# EIB_A79024-001.net
KiCad netlist of a schematic drawn in EAGLE
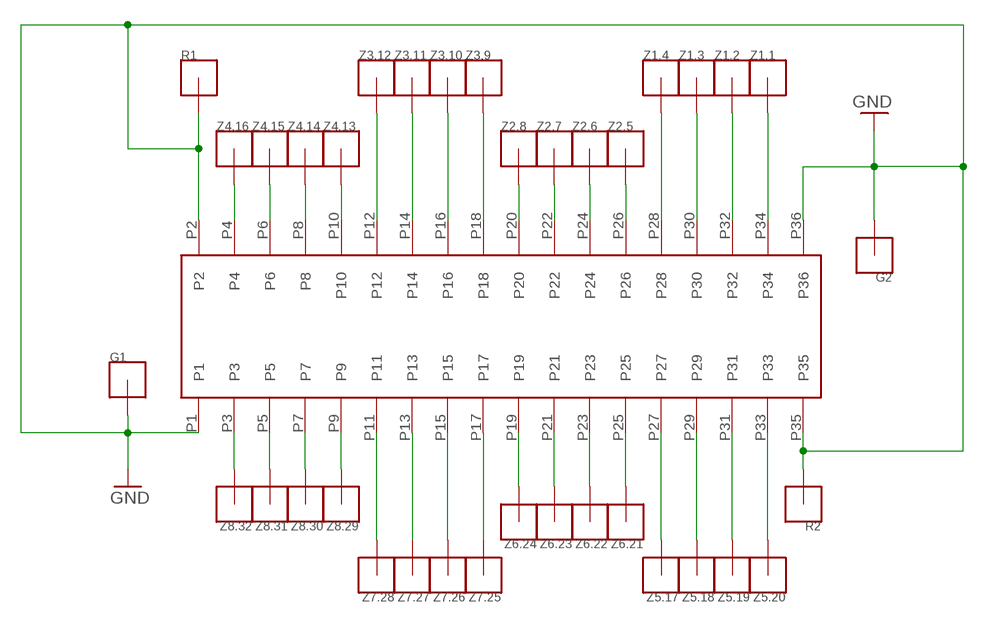
[diagram p0: schematic, sheet 1]

(export (version "E")
  (design (tool "Eeschema 10.0.6"))
  (components
    (comp (ref "A79024")
      (value "OMNETICS")
      (footprint "eagle-import:A79024")
      (libsource (lib "eagle-import") (part "OMNETICS"))
    )
    (comp (ref "G1")
      (value "S_P_HOLE")
      (footprint "eagle-import:S_P_HOLE")
      (libsource (lib "eagle-import") (part "S_P_HOLE"))
    )
    (comp (ref "G2")
      (value "S_P_HOLE")
      (footprint "eagle-import:S_P_HOLE")
      (libsource (lib "eagle-import") (part "S_P_HOLE"))
    )
    (comp (ref "R1")
      (value "S_P_HOLE")
      (footprint "eagle-import:S_P_HOLE")
      (libsource (lib "eagle-import") (part "S_P_HOLE"))
    )
    (comp (ref "R2")
      (value "S_P_HOLE")
      (footprint "eagle-import:S_P_HOLE")
      (libsource (lib "eagle-import") (part "S_P_HOLE"))
    )
    (comp (ref "Z1.1")
      (value "S_P_HOLE")
      (footprint "eagle-import:S_P_HOLE")
      (libsource (lib "eagle-import") (part "S_P_HOLE"))
    )
    (comp (ref "Z1.2")
      (value "S_P_HOLE")
      (footprint "eagle-import:S_P_HOLE")
      (libsource (lib "eagle-import") (part "S_P_HOLE"))
    )
    (comp (ref "Z1.3")
      (value "S_P_HOLE")
      (footprint "eagle-import:S_P_HOLE")
      (libsource (lib "eagle-import") (part "S_P_HOLE"))
    )
    (comp (ref "Z1.4")
      (value "S_P_HOLE")
      (footprint "eagle-import:S_P_HOLE")
      (libsource (lib "eagle-import") (part "S_P_HOLE"))
    )
    (comp (ref "Z2.5")
      (value "S_P_HOLE")
      (footprint "eagle-import:S_P_HOLE")
      (libsource (lib "eagle-import") (part "S_P_HOLE"))
    )
    (comp (ref "Z2.6")
      (value "S_P_HOLE")
      (footprint "eagle-import:S_P_HOLE")
      (libsource (lib "eagle-import") (part "S_P_HOLE"))
    )
    (comp (ref "Z2.7")
      (value "S_P_HOLE")
      (footprint "eagle-import:S_P_HOLE")
      (libsource (lib "eagle-import") (part "S_P_HOLE"))
    )
    (comp (ref "Z2.8")
      (value "S_P_HOLE")
      (footprint "eagle-import:S_P_HOLE")
      (libsource (lib "eagle-import") (part "S_P_HOLE"))
    )
    (comp (ref "Z3.9")
      (value "S_P_HOLE")
      (footprint "eagle-import:S_P_HOLE")
      (libsource (lib "eagle-import") (part "S_P_HOLE"))
    )
    (comp (ref "Z3.10")
      (value "S_P_HOLE")
      (footprint "eagle-import:S_P_HOLE")
      (libsource (lib "eagle-import") (part "S_P_HOLE"))
    )
    (comp (ref "Z3.11")
      (value "S_P_HOLE")
      (footprint "eagle-import:S_P_HOLE")
      (libsource (lib "eagle-import") (part "S_P_HOLE"))
    )
    (comp (ref "Z3.12")
      (value "S_P_HOLE")
      (footprint "eagle-import:S_P_HOLE")
      (libsource (lib "eagle-import") (part "S_P_HOLE"))
    )
    (comp (ref "Z4.13")
      (value "S_P_HOLE")
      (footprint "eagle-import:S_P_HOLE")
      (libsource (lib "eagle-import") (part "S_P_HOLE"))
    )
    (comp (ref "Z4.14")
      (value "S_P_HOLE")
      (footprint "eagle-import:S_P_HOLE")
      (libsource (lib "eagle-import") (part "S_P_HOLE"))
    )
    (comp (ref "Z4.15")
      (value "S_P_HOLE")
      (footprint "eagle-import:S_P_HOLE")
      (libsource (lib "eagle-import") (part "S_P_HOLE"))
    )
    (comp (ref "Z4.16")
      (value "S_P_HOLE")
      (footprint "eagle-import:S_P_HOLE")
      (libsource (lib "eagle-import") (part "S_P_HOLE"))
    )
    (comp (ref "Z5.17")
      (value "S_P_HOLE")
      (footprint "eagle-import:S_P_HOLE")
      (libsource (lib "eagle-import") (part "S_P_HOLE"))
    )
    (comp (ref "Z5.18")
      (value "S_P_HOLE")
      (footprint "eagle-import:S_P_HOLE")
      (libsource (lib "eagle-import") (part "S_P_HOLE"))
    )
    (comp (ref "Z5.19")
      (value "S_P_HOLE")
      (footprint "eagle-import:S_P_HOLE")
      (libsource (lib "eagle-import") (part "S_P_HOLE"))
    )
    (comp (ref "Z5.20")
      (value "S_P_HOLE")
      (footprint "eagle-import:S_P_HOLE")
      (libsource (lib "eagle-import") (part "S_P_HOLE"))
    )
    (comp (ref "Z6.21")
      (value "S_P_HOLE")
      (footprint "eagle-import:S_P_HOLE")
      (libsource (lib "eagle-import") (part "S_P_HOLE"))
    )
    (comp (ref "Z6.22")
      (value "S_P_HOLE")
      (footprint "eagle-import:S_P_HOLE")
      (libsource (lib "eagle-import") (part "S_P_HOLE"))
    )
    (comp (ref "Z6.23")
      (value "S_P_HOLE")
      (footprint "eagle-import:S_P_HOLE")
      (libsource (lib "eagle-import") (part "S_P_HOLE"))
    )
    (comp (ref "Z6.24")
      (value "S_P_HOLE")
      (footprint "eagle-import:S_P_HOLE")
      (libsource (lib "eagle-import") (part "S_P_HOLE"))
    )
    (comp (ref "Z7.25")
      (value "S_P_HOLE")
      (footprint "eagle-import:S_P_HOLE")
      (libsource (lib "eagle-import") (part "S_P_HOLE"))
    )
    (comp (ref "Z7.26")
      (value "S_P_HOLE")
      (footprint "eagle-import:S_P_HOLE")
      (libsource (lib "eagle-import") (part "S_P_HOLE"))
    )
    (comp (ref "Z7.27")
      (value "S_P_HOLE")
      (footprint "eagle-import:S_P_HOLE")
      (libsource (lib "eagle-import") (part "S_P_HOLE"))
    )
    (comp (ref "Z7.28")
      (value "S_P_HOLE")
      (footprint "eagle-import:S_P_HOLE")
      (libsource (lib "eagle-import") (part "S_P_HOLE"))
    )
    (comp (ref "Z8.29")
      (value "S_P_HOLE")
      (footprint "eagle-import:S_P_HOLE")
      (libsource (lib "eagle-import") (part "S_P_HOLE"))
    )
    (comp (ref "Z8.30")
      (value "S_P_HOLE")
      (footprint "eagle-import:S_P_HOLE")
      (libsource (lib "eagle-import") (part "S_P_HOLE"))
    )
    (comp (ref "Z8.31")
      (value "S_P_HOLE")
      (footprint "eagle-import:S_P_HOLE")
      (libsource (lib "eagle-import") (part "S_P_HOLE"))
    )
    (comp (ref "Z8.32")
      (value "S_P_HOLE")
      (footprint "eagle-import:S_P_HOLE")
      (libsource (lib "eagle-import") (part "S_P_HOLE"))
    )
  )
  (nets
    (net (code "1") (name "GND") (class "Default")
      (node (ref "A79024") (pin "P1") (pinfunction "P1_P1") (pintype "bidirectional"))
      (node (ref "A79024") (pin "P2") (pinfunction "P2_P2") (pintype "bidirectional"))
      (node (ref "A79024") (pin "P35") (pinfunction "P35_P35") (pintype "bidirectional"))
      (node (ref "A79024") (pin "P36") (pinfunction "P36_P36") (pintype "bidirectional"))
      (node (ref "G1") (pin "P1") (pinfunction "P1_P1") (pintype "bidirectional"))
      (node (ref "G2") (pin "P1") (pinfunction "P1_P1") (pintype "bidirectional"))
      (node (ref "R1") (pin "P1") (pinfunction "P1_P1") (pintype "bidirectional"))
      (node (ref "R2") (pin "P1") (pinfunction "P1_P1") (pintype "bidirectional"))
    )
    (net (code "2") (name "Net-(A79024-PadP3)") (class "Default")
      (node (ref "A79024") (pin "P3") (pinfunction "P3_P3") (pintype "bidirectional"))
      (node (ref "Z8.32") (pin "P1") (pinfunction "P1_P1") (pintype "bidirectional"))
    )
    (net (code "3") (name "Net-(A79024-PadP4)") (class "Default")
      (node (ref "A79024") (pin "P4") (pinfunction "P4_P4") (pintype "bidirectional"))
      (node (ref "Z4.16") (pin "P1") (pinfunction "P1_P1") (pintype "bidirectional"))
    )
    (net (code "4") (name "Net-(A79024-PadP5)") (class "Default")
      (node (ref "A79024") (pin "P5") (pinfunction "P5_P5") (pintype "bidirectional"))
      (node (ref "Z8.31") (pin "P1") (pinfunction "P1_P1") (pintype "bidirectional"))
    )
    (net (code "5") (name "Net-(A79024-PadP6)") (class "Default")
      (node (ref "A79024") (pin "P6") (pinfunction "P6_P6") (pintype "bidirectional"))
      (node (ref "Z4.15") (pin "P1") (pinfunction "P1_P1") (pintype "bidirectional"))
    )
    (net (code "6") (name "Net-(A79024-PadP7)") (class "Default")
      (node (ref "A79024") (pin "P7") (pinfunction "P7_P7") (pintype "bidirectional"))
      (node (ref "Z8.30") (pin "P1") (pinfunction "P1_P1") (pintype "bidirectional"))
    )
    (net (code "7") (name "Net-(A79024-PadP8)") (class "Default")
      (node (ref "A79024") (pin "P8") (pinfunction "P8_P8") (pintype "bidirectional"))
      (node (ref "Z4.14") (pin "P1") (pinfunction "P1_P1") (pintype "bidirectional"))
    )
    (net (code "8") (name "Net-(A79024-PadP9)") (class "Default")
      (node (ref "A79024") (pin "P9") (pinfunction "P9_P9") (pintype "bidirectional"))
      (node (ref "Z8.29") (pin "P1") (pinfunction "P1_P1") (pintype "bidirectional"))
    )
    (net (code "9") (name "Net-(A79024-PadP10)") (class "Default")
      (node (ref "A79024") (pin "P10") (pinfunction "P10_P10") (pintype "bidirectional"))
      (node (ref "Z4.13") (pin "P1") (pinfunction "P1_P1") (pintype "bidirectional"))
    )
    (net (code "10") (name "Net-(A79024-PadP11)") (class "Default")
      (node (ref "A79024") (pin "P11") (pinfunction "P11_P11") (pintype "bidirectional"))
      (node (ref "Z7.28") (pin "P1") (pinfunction "P1_P1") (pintype "bidirectional"))
    )
    (net (code "11") (name "Net-(A79024-PadP12)") (class "Default")
      (node (ref "A79024") (pin "P12") (pinfunction "P12_P12") (pintype "bidirectional"))
      (node (ref "Z3.12") (pin "P1") (pinfunction "P1_P1") (pintype "bidirectional"))
    )
    (net (code "12") (name "Net-(A79024-PadP13)") (class "Default")
      (node (ref "A79024") (pin "P13") (pinfunction "P13_P13") (pintype "bidirectional"))
      (node (ref "Z7.27") (pin "P1") (pinfunction "P1_P1") (pintype "bidirectional"))
    )
    (net (code "13") (name "Net-(A79024-PadP14)") (class "Default")
      (node (ref "A79024") (pin "P14") (pinfunction "P14_P14") (pintype "bidirectional"))
      (node (ref "Z3.11") (pin "P1") (pinfunction "P1_P1") (pintype "bidirectional"))
    )
    (net (code "14") (name "Net-(A79024-PadP15)") (class "Default")
      (node (ref "A79024") (pin "P15") (pinfunction "P15_P15") (pintype "bidirectional"))
      (node (ref "Z7.26") (pin "P1") (pinfunction "P1_P1") (pintype "bidirectional"))
    )
    (net (code "15") (name "Net-(A79024-PadP16)") (class "Default")
      (node (ref "A79024") (pin "P16") (pinfunction "P16_P16") (pintype "bidirectional"))
      (node (ref "Z3.10") (pin "P1") (pinfunction "P1_P1") (pintype "bidirectional"))
    )
    (net (code "16") (name "Net-(A79024-PadP17)") (class "Default")
      (node (ref "A79024") (pin "P17") (pinfunction "P17_P17") (pintype "bidirectional"))
      (node (ref "Z7.25") (pin "P1") (pinfunction "P1_P1") (pintype "bidirectional"))
    )
    (net (code "17") (name "Net-(A79024-PadP18)") (class "Default")
      (node (ref "A79024") (pin "P18") (pinfunction "P18_P18") (pintype "bidirectional"))
      (node (ref "Z3.9") (pin "P1") (pinfunction "P1_P1") (pintype "bidirectional"))
    )
    (net (code "18") (name "Net-(A79024-PadP19)") (class "Default")
      (node (ref "A79024") (pin "P19") (pinfunction "P19_P19") (pintype "bidirectional"))
      (node (ref "Z6.24") (pin "P1") (pinfunction "P1_P1") (pintype "bidirectional"))
    )
    (net (code "19") (name "Net-(A79024-PadP20)") (class "Default")
      (node (ref "A79024") (pin "P20") (pinfunction "P20_P20") (pintype "bidirectional"))
      (node (ref "Z2.8") (pin "P1") (pinfunction "P1_P1") (pintype "bidirectional"))
    )
    (net (code "20") (name "Net-(A79024-PadP21)") (class "Default")
      (node (ref "A79024") (pin "P21") (pinfunction "P21_P21") (pintype "bidirectional"))
      (node (ref "Z6.23") (pin "P1") (pinfunction "P1_P1") (pintype "bidirectional"))
    )
    (net (code "21") (name "Net-(A79024-PadP22)") (class "Default")
      (node (ref "A79024") (pin "P22") (pinfunction "P22_P22") (pintype "bidirectional"))
      (node (ref "Z2.7") (pin "P1") (pinfunction "P1_P1") (pintype "bidirectional"))
    )
    (net (code "22") (name "Net-(A79024-PadP23)") (class "Default")
      (node (ref "A79024") (pin "P23") (pinfunction "P23_P23") (pintype "bidirectional"))
      (node (ref "Z6.22") (pin "P1") (pinfunction "P1_P1") (pintype "bidirectional"))
    )
    (net (code "23") (name "Net-(A79024-PadP24)") (class "Default")
      (node (ref "A79024") (pin "P24") (pinfunction "P24_P24") (pintype "bidirectional"))
      (node (ref "Z2.6") (pin "P1") (pinfunction "P1_P1") (pintype "bidirectional"))
    )
    (net (code "24") (name "Net-(A79024-PadP25)") (class "Default")
      (node (ref "A79024") (pin "P25") (pinfunction "P25_P25") (pintype "bidirectional"))
      (node (ref "Z6.21") (pin "P1") (pinfunction "P1_P1") (pintype "bidirectional"))
    )
    (net (code "25") (name "Net-(A79024-PadP26)") (class "Default")
      (node (ref "A79024") (pin "P26") (pinfunction "P26_P26") (pintype "bidirectional"))
      (node (ref "Z2.5") (pin "P1") (pinfunction "P1_P1") (pintype "bidirectional"))
    )
    (net (code "26") (name "Net-(A79024-PadP27)") (class "Default")
      (node (ref "A79024") (pin "P27") (pinfunction "P27_P27") (pintype "bidirectional"))
      (node (ref "Z5.17") (pin "P1") (pinfunction "P1_P1") (pintype "bidirectional"))
    )
    (net (code "27") (name "Net-(A79024-PadP28)") (class "Default")
      (node (ref "A79024") (pin "P28") (pinfunction "P28_P28") (pintype "bidirectional"))
      (node (ref "Z1.4") (pin "P1") (pinfunction "P1_P1") (pintype "bidirectional"))
    )
    (net (code "28") (name "Net-(A79024-PadP29)") (class "Default")
      (node (ref "A79024") (pin "P29") (pinfunction "P29_P29") (pintype "bidirectional"))
      (node (ref "Z5.18") (pin "P1") (pinfunction "P1_P1") (pintype "bidirectional"))
    )
    (net (code "29") (name "Net-(A79024-PadP30)") (class "Default")
      (node (ref "A79024") (pin "P30") (pinfunction "P30_P30") (pintype "bidirectional"))
      (node (ref "Z1.3") (pin "P1") (pinfunction "P1_P1") (pintype "bidirectional"))
    )
    (net (code "30") (name "Net-(A79024-PadP31)") (class "Default")
      (node (ref "A79024") (pin "P31") (pinfunction "P31_P31") (pintype "bidirectional"))
      (node (ref "Z5.19") (pin "P1") (pinfunction "P1_P1") (pintype "bidirectional"))
    )
    (net (code "31") (name "Net-(A79024-PadP32)") (class "Default")
      (node (ref "A79024") (pin "P32") (pinfunction "P32_P32") (pintype "bidirectional"))
      (node (ref "Z1.2") (pin "P1") (pinfunction "P1_P1") (pintype "bidirectional"))
    )
    (net (code "32") (name "Net-(A79024-PadP33)") (class "Default")
      (node (ref "A79024") (pin "P33") (pinfunction "P33_P33") (pintype "bidirectional"))
      (node (ref "Z5.20") (pin "P1") (pinfunction "P1_P1") (pintype "bidirectional"))
    )
    (net (code "33") (name "Net-(A79024-PadP34)") (class "Default")
      (node (ref "A79024") (pin "P34") (pinfunction "P34_P34") (pintype "bidirectional"))
      (node (ref "Z1.1") (pin "P1") (pinfunction "P1_P1") (pintype "bidirectional"))
    )
  )
)
